# VoltageMeasurement.net
KiCad netlist of a schematic drawn in Altium Designer
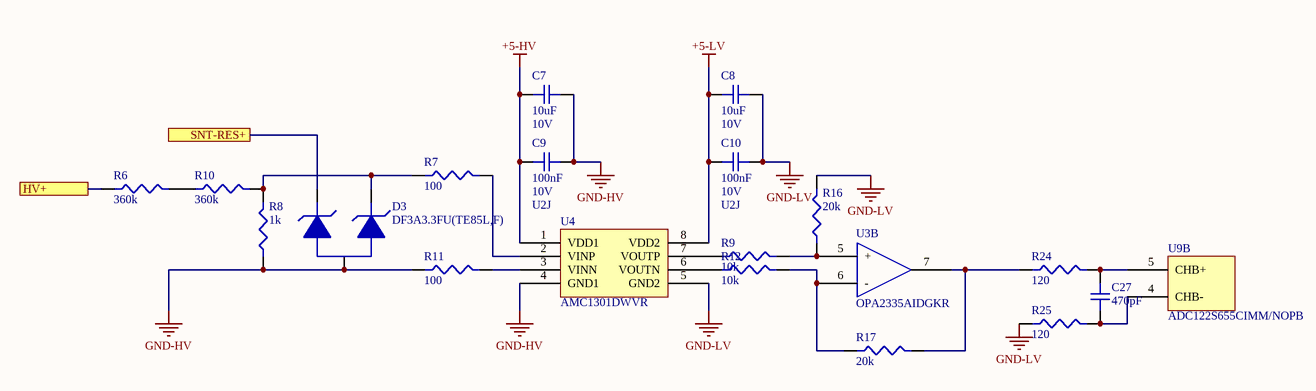
[diagram p0: VoltageMeasurement.SchDoc]

(export (version "E")
  (design (tool "Eeschema 10.0.6"))
  (components
    (comp (ref "C7")
      (value "10uF")
      (footprint "TANT_10u")
      (fields
        (field (name "MANUFACTURER") "Kyocera AVX")
        (field (name "MANUFACTURER PART NUMBER") "F381A106MMA")
        (field (name "TOLERANCE") "20%")
        (field (name "VOLTAGE RATING") "10V")
      )
      (libsource (lib "PHANTOM_LIBRARY") (part "F381A106MMA"))
    )
    (comp (ref "C8")
      (value "10uF")
      (footprint "TANT_10u")
      (fields
        (field (name "MANUFACTURER") "Kyocera AVX")
        (field (name "MANUFACTURER PART NUMBER") "F381A106MMA")
        (field (name "TOLERANCE") "20%")
        (field (name "VOLTAGE RATING") "10V")
      )
      (libsource (lib "PHANTOM_LIBRARY") (part "F381A106MMA"))
    )
    (comp (ref "C9")
      (value "100nF")
      (footprint "PHANTOM_FOOTPRINTS:C0805")
      (description "CAP MLCC 100nF 10Volts U2J 5%")
      (fields
        (field (name "MANUFACTURER") "Murata")
        (field (name "MANUFACTURER PART NUMBER") "GRM21B7U1A104JA01L")
        (field (name "VOLTAGE RATING") "10V")
        (field (name "DIELECTRIC") "U2J")
      )
      (libsource (lib "PHANTOM_LIBRARY") (part "GRM21B7U1A104JA01L"))
    )
    (comp (ref "C10")
      (value "100nF")
      (footprint "PHANTOM_FOOTPRINTS:C0805")
      (description "CAP MLCC 100nF 10Volts U2J 5%")
      (fields
        (field (name "MANUFACTURER") "Murata")
        (field (name "MANUFACTURER PART NUMBER") "GRM21B7U1A104JA01L")
        (field (name "VOLTAGE RATING") "10V")
        (field (name "DIELECTRIC") "U2J")
      )
      (libsource (lib "PHANTOM_LIBRARY") (part "GRM21B7U1A104JA01L"))
    )
    (comp (ref "C27")
      (value "470pF")
      (footprint "C0805")
      (description "CAP  470pF ±5% 250V Ceramic Capacitor U2J 0805 (2012 Metric)")
      (fields
        (field (name "MANUFACTURER") "Murata")
        (field (name "MANUFACTURER PART NUMBER") "GRM21A7U2E471JW31D")
      )
      (libsource (lib "PHANTOM_LIBRARY") (part "GRM21A7U2E471JW31D"))
    )
    (comp (ref "D3")
      (value "DF3A3.3FU(TE85L,F)")
      (footprint "DIODE_TVS_2channel")
      (description "TVS diode 12V, 20V Clamp 60A (8/20µs) Ipp Tvs Diode Surface Mount 1610")
      (fields (field (name "MANUFACTURER") "Toshiba Semiconductor"))
      (libsource (lib "PHANTOM_LIBRARY") (part "DF3A3.3FU(TE85L,F)"))
    )
    (comp (ref "R6")
      (value "360k")
      (footprint "R0805")
      (description "RES SMD 360k OHM 0805 360k Ohm 0.1% 0.125W(1/8W) ±25ppm/C Molded SMD Automotive Punched T/R")
      (fields
        (field (name "MANUFACTURER") "Panasonic ECG")
        (field (name "MANUFACTURER PART NUMBER") "ERA-6AEB102V")
      )
      (libsource (lib "PHANTOM_LIBRARY") (part "ERA-6AEB364V"))
    )
    (comp (ref "R7")
      (value "100")
      (footprint "R0805")
      (description "RES SMD 100 OHM 0805 100 Ohm 0.1% 0.125W(1/8W) ±25ppm/C Molded SMD Automotive Punched T/R")
      (fields
        (field (name "MANUFACTURER") "Panasonic ECG")
        (field (name "MANUFACTURER PART NUMBER") "ERA-6AEB102V")
      )
      (libsource (lib "PHANTOM_LIBRARY") (part "ERA-6AEB101V"))
    )
    (comp (ref "R8")
      (value "1k")
      (footprint "R0805")
      (description "RES SMD 1K OHM 0805 1K Ohm 0.1% 0.125W(1/8W) ±25ppm/C Molded SMD Automotive Punched T/R")
      (fields
        (field (name "MANUFACTURER") "Panasonic ECG")
        (field (name "MANUFACTURER PART NUMBER") "ERA-6AEB102V")
      )
      (libsource (lib "PHANTOM_LIBRARY") (part "ERA-6AEB102V"))
    )
    (comp (ref "R9")
      (value "10k")
      (footprint "R0805")
      (description "RES SMD 10K OHM 1% 1/8W 0805")
      (fields
        (field (name "MANUFACTURER") "Yageo Phycomp")
        (field (name "MANUFACTURER PART NUMBER") "RC0805FR-071KL")
      )
      (libsource (lib "PHANTOM_LIBRARY") (part "RC0805FR-071KL"))
    )
    (comp (ref "R10")
      (value "360k")
      (footprint "R0805")
      (description "RES SMD 360k OHM 0805 360k Ohm 0.1% 0.125W(1/8W) ±25ppm/C Molded SMD Automotive Punched T/R")
      (fields
        (field (name "MANUFACTURER") "Panasonic ECG")
        (field (name "MANUFACTURER PART NUMBER") "ERA-6AEB102V")
      )
      (libsource (lib "PHANTOM_LIBRARY") (part "ERA-6AEB364V"))
    )
    (comp (ref "R11")
      (value "100")
      (footprint "R0805")
      (description "RES SMD 100 OHM 0805 100 Ohm 0.1% 0.125W(1/8W) ±25ppm/C Molded SMD Automotive Punched T/R")
      (fields
        (field (name "MANUFACTURER") "Panasonic ECG")
        (field (name "MANUFACTURER PART NUMBER") "ERA-6AEB102V")
      )
      (libsource (lib "PHANTOM_LIBRARY") (part "ERA-6AEB101V"))
    )
    (comp (ref "R12")
      (value "10k")
      (footprint "R0805")
      (description "RES SMD 10K OHM 1% 1/8W 0805")
      (fields
        (field (name "MANUFACTURER") "Yageo Phycomp")
        (field (name "MANUFACTURER PART NUMBER") "RC0805FR-071KL")
      )
      (libsource (lib "PHANTOM_LIBRARY") (part "RC0805FR-071KL"))
    )
    (comp (ref "R16")
      (value "20k")
      (footprint "R0805")
      (description "RES SMD 20K OHM 0805 20K Ohm 0.1% 0.125W(1/8W) ±25ppm/C Molded SMD Automotive Punched T/R")
      (fields
        (field (name "MANUFACTURER") "Panasonic ECG")
        (field (name "MANUFACTURER PART NUMBER") "ERA-6AEB102V")
      )
      (libsource (lib "PHANTOM_LIBRARY") (part "ERA-6AEB203V"))
    )
    (comp (ref "R17")
      (value "20k")
      (footprint "R0805")
      (description "RES SMD 20K OHM 0805 20K Ohm 0.1% 0.125W(1/8W) ±25ppm/C Molded SMD Automotive Punched T/R")
      (fields
        (field (name "MANUFACTURER") "Panasonic ECG")
        (field (name "MANUFACTURER PART NUMBER") "ERA-6AEB102V")
      )
      (libsource (lib "PHANTOM_LIBRARY") (part "ERA-6AEB203V"))
    )
    (comp (ref "R24")
      (value "120")
      (footprint "R0805")
      (description "RES SMD 120 OHM 1% 1/8W 0805")
      (fields
        (field (name "MANUFACTURER") "Yageo")
        (field (name "MANUFACTURER PART NUMBER") "RC0805FR-07120RL")
      )
      (libsource (lib "PHANTOM_LIBRARY") (part "RC0805FR-07120RL"))
    )
    (comp (ref "R25")
      (value "120")
      (footprint "R0805")
      (description "RES SMD 120 OHM 1% 1/8W 0805")
      (fields
        (field (name "MANUFACTURER") "Yageo")
        (field (name "MANUFACTURER PART NUMBER") "RC0805FR-07120RL")
      )
      (libsource (lib "PHANTOM_LIBRARY") (part "RC0805FR-07120RL"))
    )
    (comp (ref "U3")
      (value "OPA2335AIDGKR")
      (footprint "8-VSSOP-OPA2335AIDGKR")
      (description "IC OPAMP ZERO-DRIFT 2CIRC 8VSSOP")
      (fields (field (name "MANUFACTURER") "Texas Instruments"))
      (libsource (lib "PHANTOM_LIBRARY") (part "OPA2335AIDGKR"))
    )
    (comp (ref "U4")
      (value "AMC1301DWVR")
      (footprint "8-SOIC-AMC1301DWVR")
      (description "IC OPAMP ISOLATION 1 CIRC 8 SOIC")
      (fields (field (name "MANUFACTURER") "Texas Instruments"))
      (libsource (lib "PHANTOM_LIBRARY") (part "AMC1301DWVR"))
    )
    (comp (ref "U9")
      (value "ADC122S655CIMM/NOPB")
      (footprint "10-VSSOP-ADC122S655CIMM/NOPB")
      (description "12 Bit Analog to Digital Converter 2 Input 2 SAR 10-VSSOP")
      (fields (field (name "MANUFACTURER") "Texas Instruments"))
      (libsource (lib "PHANTOM_LIBRARY") (part "ADC122S655CIMM/NOPB"))
    )
  )
  (nets
    (net (code "1") (name "+5-HV") (class "Default")
      (node (ref "C7") (pin "1") (pinfunction "1_1") (pintype "passive"))
      (node (ref "C9") (pin "1") (pinfunction "1_1") (pintype "passive"))
      (node (ref "U4") (pin "1") (pinfunction "VDD1_1") (pintype "passive"))
    )
    (net (code "2") (name "+5-LV") (class "Default")
      (node (ref "C10") (pin "1") (pinfunction "1_1") (pintype "passive"))
      (node (ref "C8") (pin "1") (pinfunction "1_1") (pintype "passive"))
      (node (ref "U4") (pin "8") (pinfunction "VDD2_8") (pintype "passive"))
    )
    (net (code "3") (name "/HV+") (class "Default")
      (node (ref "R6") (pin "1") (pinfunction "1_1") (pintype "passive"))
    )
    (net (code "4") (name "/SNT-RES+") (class "Default")
      (node (ref "D3") (pin "2") (pinfunction "2_2") (pintype "passive"))
    )
    (net (code "5") (name "GND-HV") (class "Default")
      (node (ref "C7") (pin "2") (pinfunction "2_2") (pintype "passive"))
      (node (ref "C9") (pin "2") (pinfunction "2_2") (pintype "passive"))
      (node (ref "D3") (pin "3") (pinfunction "1_3") (pintype "passive"))
      (node (ref "R11") (pin "1") (pinfunction "1_1") (pintype "passive"))
      (node (ref "R8") (pin "1") (pinfunction "1_1") (pintype "passive"))
      (node (ref "U4") (pin "4") (pinfunction "GND1_4") (pintype "passive"))
    )
    (net (code "6") (name "GND-LV") (class "Default")
      (node (ref "C10") (pin "2") (pinfunction "2_2") (pintype "passive"))
      (node (ref "C8") (pin "2") (pinfunction "2_2") (pintype "passive"))
      (node (ref "R16") (pin "2") (pinfunction "2_2") (pintype "passive"))
      (node (ref "R25") (pin "1") (pinfunction "1_1") (pintype "passive"))
      (node (ref "U4") (pin "5") (pinfunction "GND2_5") (pintype "passive"))
    )
    (net (code "7") (name "Net-(D3-2-Pad1)") (class "Default")
      (node (ref "D3") (pin "1") (pinfunction "2_1") (pintype "passive"))
      (node (ref "R10") (pin "2") (pinfunction "2_2") (pintype "passive"))
      (node (ref "R7") (pin "1") (pinfunction "1_1") (pintype "passive"))
      (node (ref "R8") (pin "2") (pinfunction "2_2") (pintype "passive"))
    )
    (net (code "8") (name "Net-(R10-Pad1)") (class "Default")
      (node (ref "R10") (pin "1") (pinfunction "1_1") (pintype "passive"))
      (node (ref "R6") (pin "2") (pinfunction "2_2") (pintype "passive"))
    )
    (net (code "9") (name "Net-(U3B-+)") (class "Default")
      (node (ref "R16") (pin "1") (pinfunction "1_1") (pintype "passive"))
      (node (ref "R9") (pin "2") (pinfunction "2_2") (pintype "passive"))
      (node (ref "U3") (pin "5") (pinfunction "+_5") (pintype "passive"))
    )
    (net (code "10") (name "Net-(U3B--)") (class "Default")
      (node (ref "R12") (pin "2") (pinfunction "2_2") (pintype "passive"))
      (node (ref "R17") (pin "1") (pinfunction "1_1") (pintype "passive"))
      (node (ref "U3") (pin "6") (pinfunction "-_6") (pintype "passive"))
    )
    (net (code "11") (name "Net-(U3B-OutB)") (class "Default")
      (node (ref "R17") (pin "2") (pinfunction "2_2") (pintype "passive"))
      (node (ref "R24") (pin "1") (pinfunction "1_1") (pintype "passive"))
      (node (ref "U3") (pin "7") (pinfunction "OutB_7") (pintype "passive"))
    )
    (net (code "12") (name "Net-(U4-VINN)") (class "Default")
      (node (ref "R11") (pin "2") (pinfunction "2_2") (pintype "passive"))
      (node (ref "U4") (pin "3") (pinfunction "VINN_3") (pintype "passive"))
    )
    (net (code "13") (name "Net-(U4-VINP)") (class "Default")
      (node (ref "R7") (pin "2") (pinfunction "2_2") (pintype "passive"))
      (node (ref "U4") (pin "2") (pinfunction "VINP_2") (pintype "passive"))
    )
    (net (code "14") (name "Net-(U4-VOUTN)") (class "Default")
      (node (ref "R12") (pin "1") (pinfunction "1_1") (pintype "passive"))
      (node (ref "U4") (pin "6") (pinfunction "VOUTN_6") (pintype "passive"))
    )
    (net (code "15") (name "Net-(U4-VOUTP)") (class "Default")
      (node (ref "R9") (pin "1") (pinfunction "1_1") (pintype "passive"))
      (node (ref "U4") (pin "7") (pinfunction "VOUTP_7") (pintype "passive"))
    )
    (net (code "16") (name "Net-(U9B-CHB+)") (class "Default")
      (node (ref "C27") (pin "2") (pinfunction "2_2") (pintype "passive"))
      (node (ref "R24") (pin "2") (pinfunction "2_2") (pintype "passive"))
      (node (ref "U9") (pin "5") (pinfunction "CHB+_5") (pintype "passive"))
    )
    (net (code "17") (name "Net-(U9B-CHB-)") (class "Default")
      (node (ref "C27") (pin "1") (pinfunction "1_1") (pintype "passive"))
      (node (ref "R25") (pin "2") (pinfunction "2_2") (pintype "passive"))
      (node (ref "U9") (pin "4") (pinfunction "CHB-_4") (pintype "passive"))
    )
  )
)
